# 11_-_CPU_-_POWER.net
KiCad netlist of a schematic drawn in Altium Designer
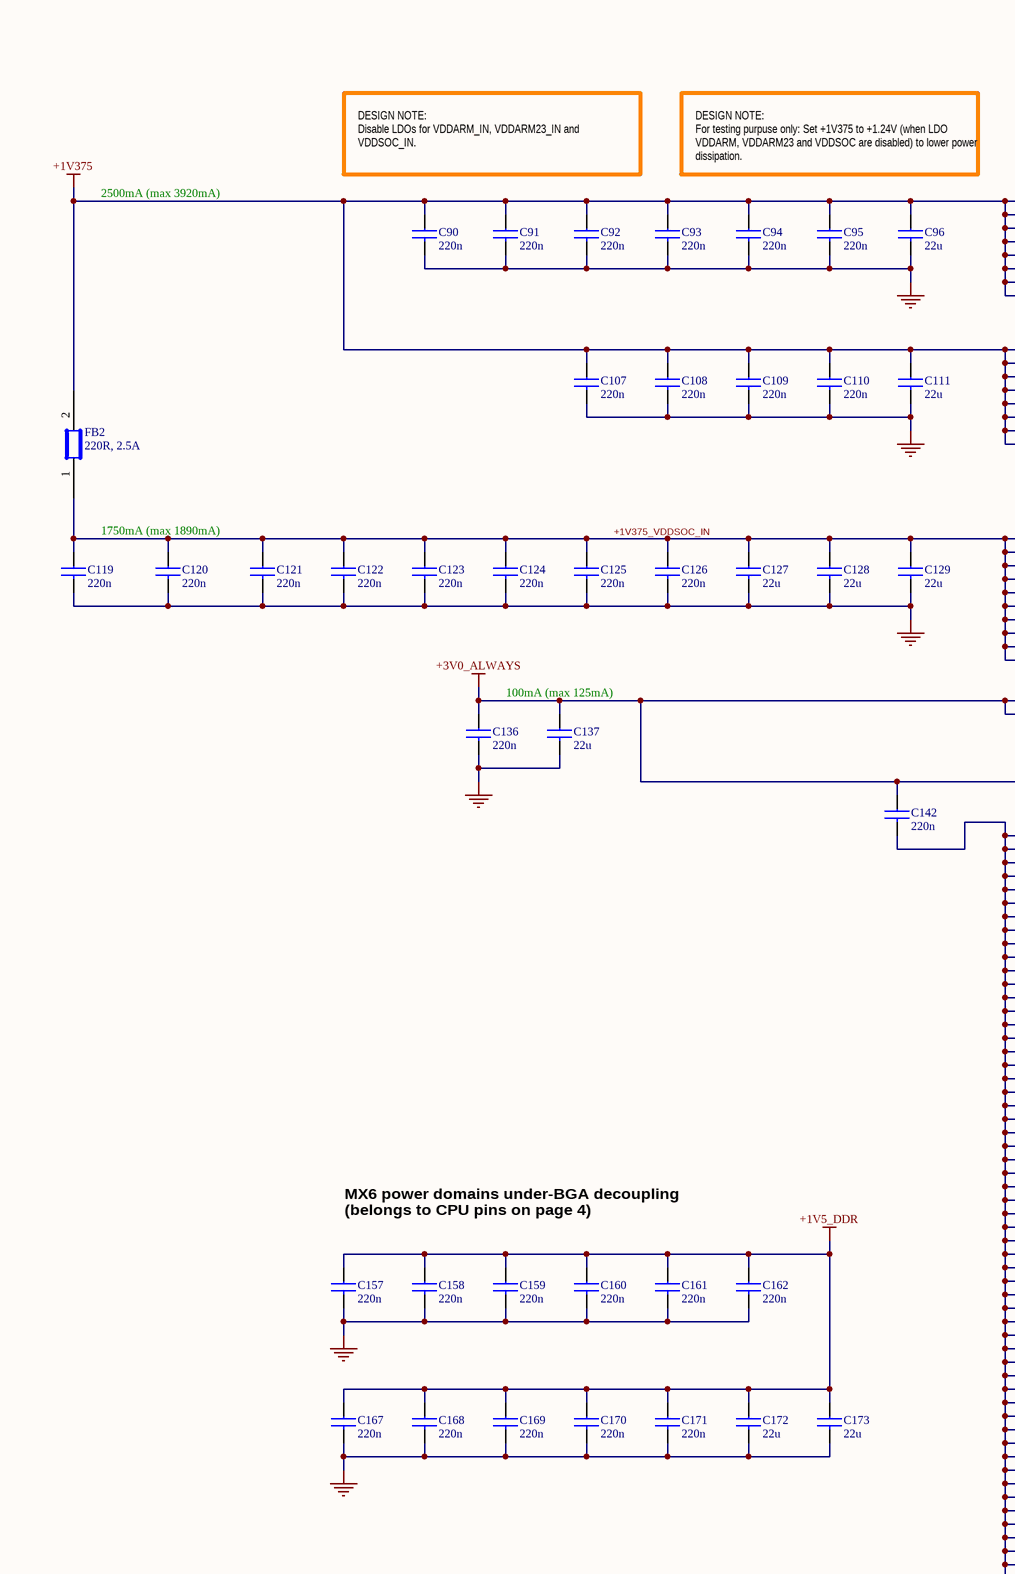
[diagram p0: [11] - CPU - POWER.SchDoc, left]
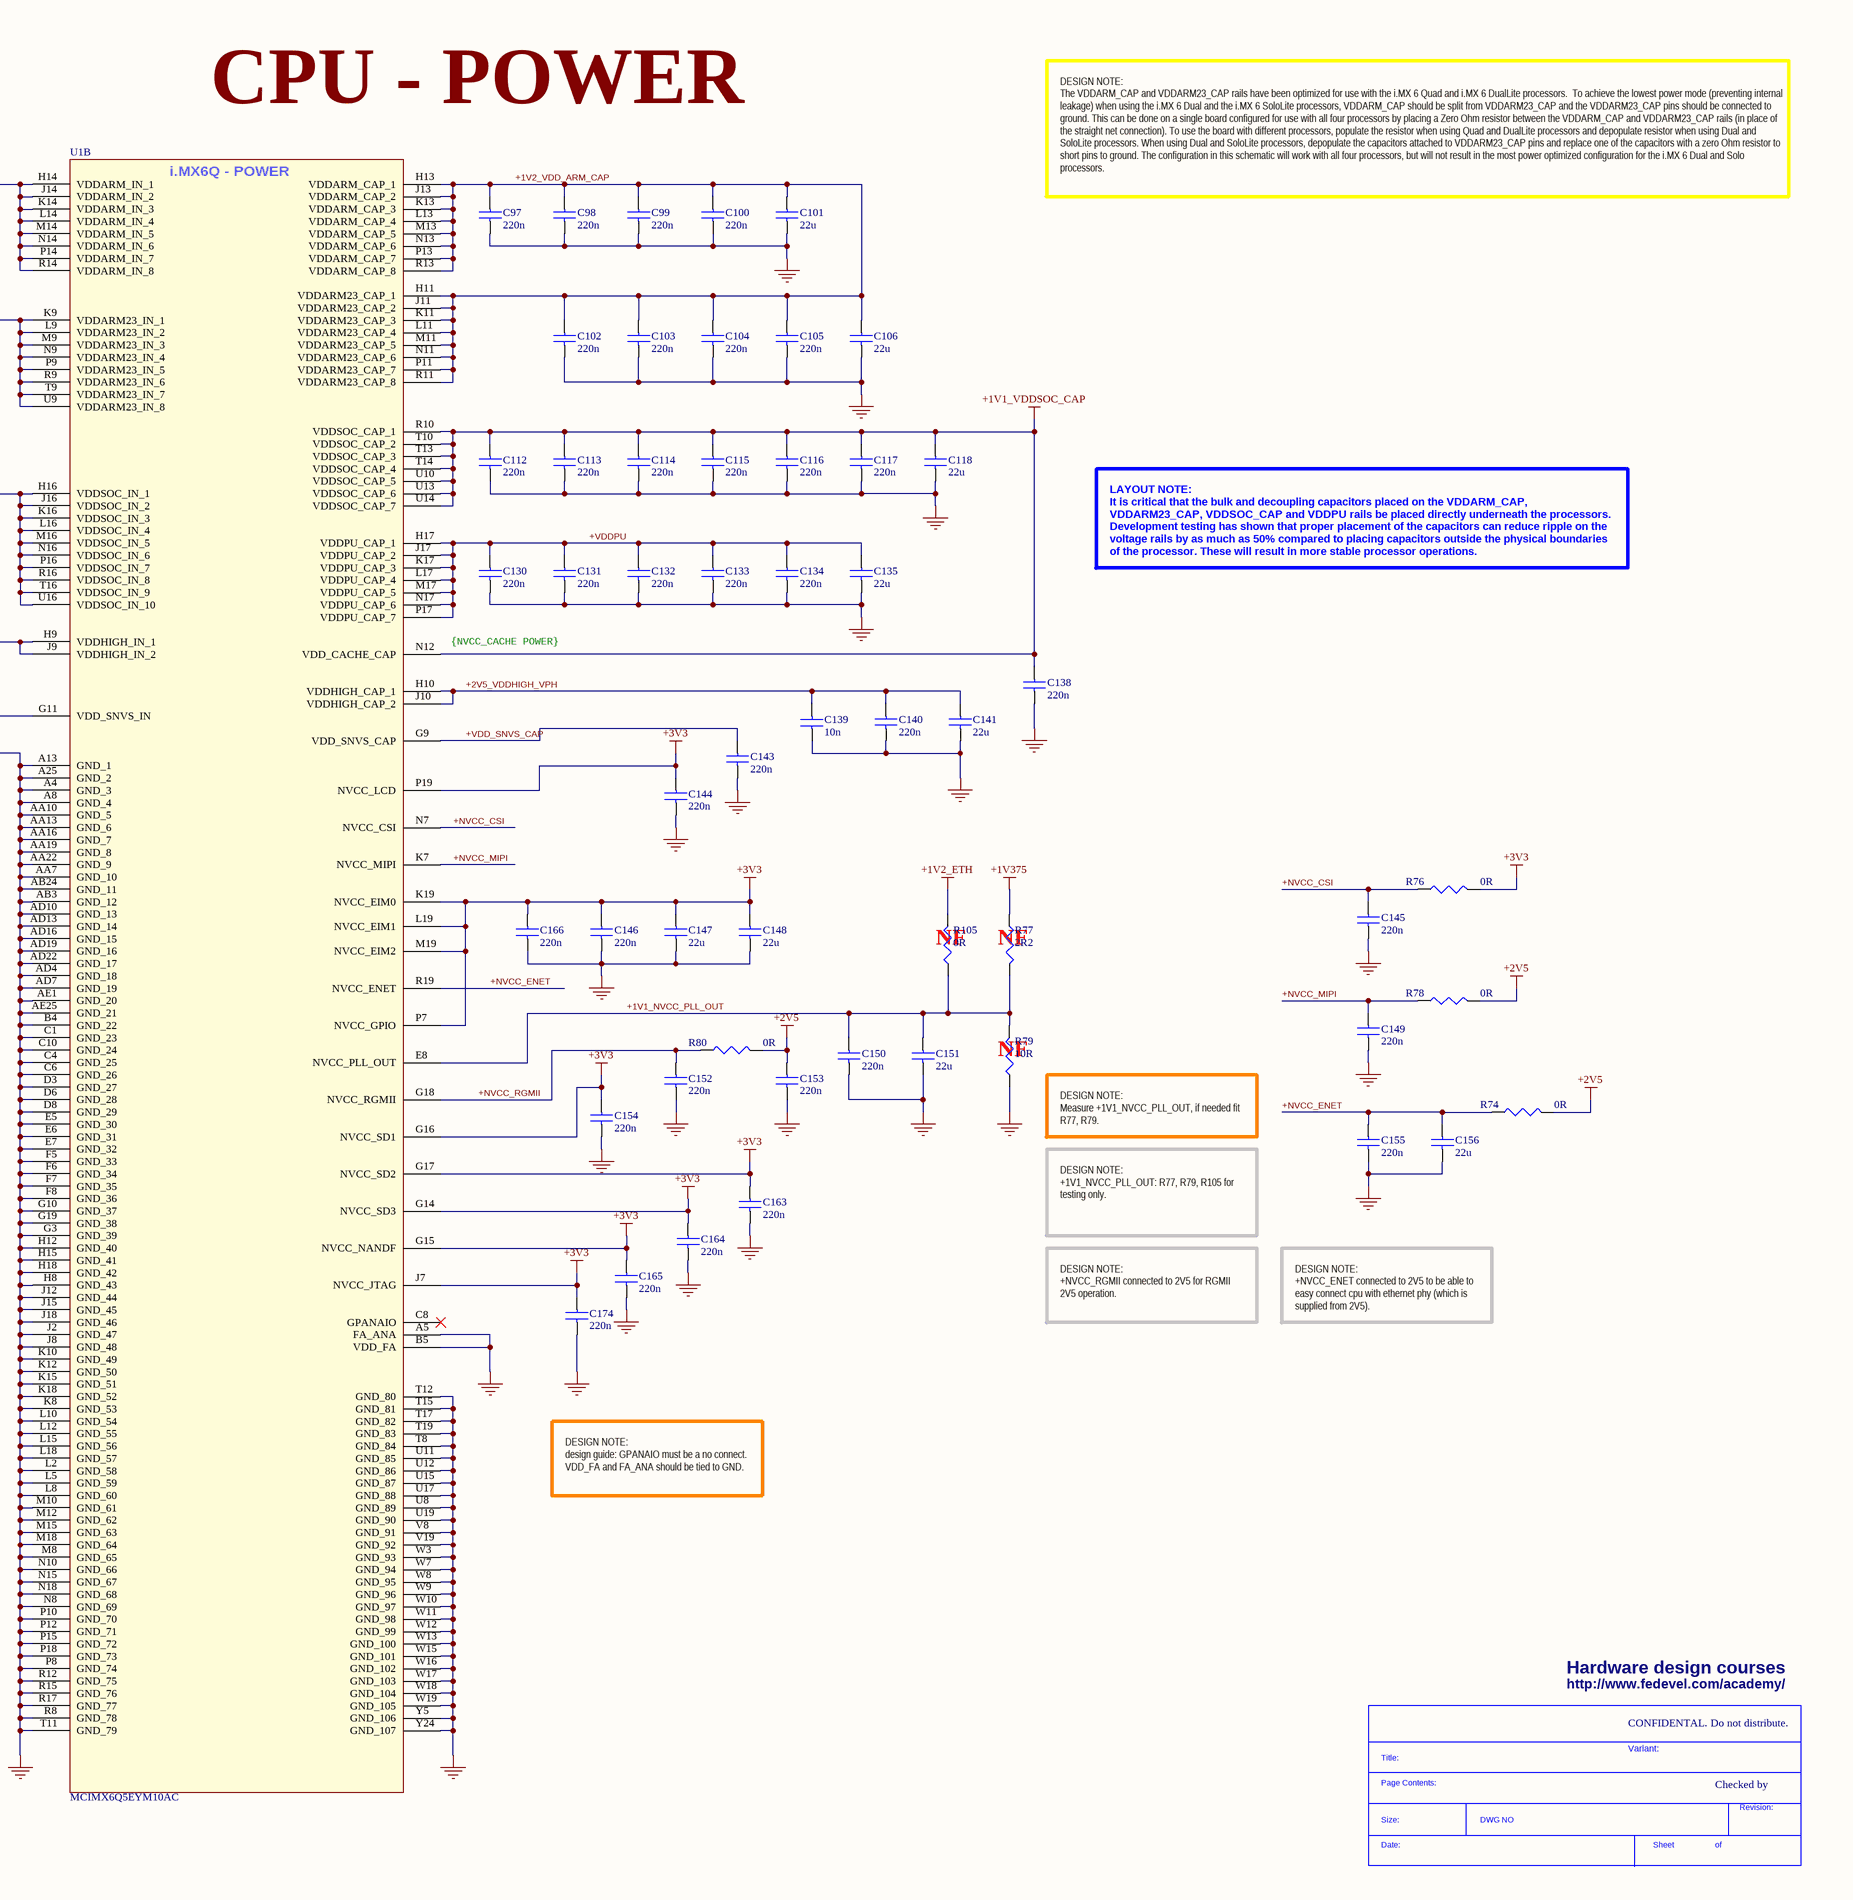
[diagram p1: [11] - CPU - POWER.SchDoc, right]

(export (version "E")
  (design (tool "Eeschema 10.0.6"))
  (components
    (comp (ref "C90")
      (value "220n")
      (footprint "C0402")
      (description "CAP CER .22UF 25V X5R 20% 0402")
      (fields
        (field (name "MANUFACTURER") "TDK Corporation")
        (field (name "MANUFACTURER PART NUMBER") "C1005X5R1E224M")
      )
      (libsource (lib "iMX6 Rex_V1I1") (part "C1005X5R1E224M"))
    )
    (comp (ref "C91")
      (value "220n")
      (footprint "C0402")
      (description "CAP CER .22UF 25V X5R 20% 0402")
      (fields
        (field (name "MANUFACTURER") "TDK Corporation")
        (field (name "MANUFACTURER PART NUMBER") "C1005X5R1E224M")
      )
      (libsource (lib "iMX6 Rex_V1I1") (part "C1005X5R1E224M"))
    )
    (comp (ref "C92")
      (value "220n")
      (footprint "C0402")
      (description "CAP CER .22UF 25V X5R 20% 0402")
      (fields
        (field (name "MANUFACTURER") "TDK Corporation")
        (field (name "MANUFACTURER PART NUMBER") "C1005X5R1E224M")
      )
      (libsource (lib "iMX6 Rex_V1I1") (part "C1005X5R1E224M"))
    )
    (comp (ref "C93")
      (value "220n")
      (footprint "C0402")
      (description "CAP CER .22UF 25V X5R 20% 0402")
      (fields
        (field (name "MANUFACTURER") "TDK Corporation")
        (field (name "MANUFACTURER PART NUMBER") "C1005X5R1E224M")
      )
      (libsource (lib "iMX6 Rex_V1I1") (part "C1005X5R1E224M"))
    )
    (comp (ref "C94")
      (value "220n")
      (footprint "C0402")
      (description "CAP CER .22UF 25V X5R 20% 0402")
      (fields
        (field (name "MANUFACTURER") "TDK Corporation")
        (field (name "MANUFACTURER PART NUMBER") "C1005X5R1E224M")
      )
      (libsource (lib "iMX6 Rex_V1I1") (part "C1005X5R1E224M"))
    )
    (comp (ref "C95")
      (value "220n")
      (footprint "C0402")
      (description "CAP CER .22UF 25V X5R 20% 0402")
      (fields
        (field (name "MANUFACTURER") "TDK Corporation")
        (field (name "MANUFACTURER PART NUMBER") "C1005X5R1E224M")
      )
      (libsource (lib "iMX6 Rex_V1I1") (part "C1005X5R1E224M"))
    )
    (comp (ref "C96")
      (value "22u")
      (footprint "C0603")
      (description "CAP CER 22UF 4V 20% X5R 0603")
      (fields
        (field (name "MANUFACTURER") "Murata Electronics North America")
        (field (name "MANUFACTURER PART NUMBER") "GRM188R60G226MEA0L")
        (field (name ".CHECKED PCB") "RF, used by MM")
        (field (name ".CHECKED SCH") "MM, checked by RF")
        (field (name ".CREATOR") "MM")
      )
      (libsource (lib "iMX6 Rex_V1I1") (part "GRM188R60G226MEA0L"))
    )
    (comp (ref "C97")
      (value "220n")
      (footprint "C0402")
      (description "CAP CER .22UF 25V X5R 20% 0402")
      (fields
        (field (name "MANUFACTURER") "TDK Corporation")
        (field (name "MANUFACTURER PART NUMBER") "C1005X5R1E224M")
      )
      (libsource (lib "iMX6 Rex_V1I1") (part "C1005X5R1E224M"))
    )
    (comp (ref "C98")
      (value "220n")
      (footprint "C0402")
      (description "CAP CER .22UF 25V X5R 20% 0402")
      (fields
        (field (name "MANUFACTURER") "TDK Corporation")
        (field (name "MANUFACTURER PART NUMBER") "C1005X5R1E224M")
      )
      (libsource (lib "iMX6 Rex_V1I1") (part "C1005X5R1E224M"))
    )
    (comp (ref "C99")
      (value "220n")
      (footprint "C0402")
      (description "CAP CER .22UF 25V X5R 20% 0402")
      (fields
        (field (name "MANUFACTURER") "TDK Corporation")
        (field (name "MANUFACTURER PART NUMBER") "C1005X5R1E224M")
      )
      (libsource (lib "iMX6 Rex_V1I1") (part "C1005X5R1E224M"))
    )
    (comp (ref "C100")
      (value "220n")
      (footprint "C0402")
      (description "CAP CER .22UF 25V X5R 20% 0402")
      (fields
        (field (name "MANUFACTURER") "TDK Corporation")
        (field (name "MANUFACTURER PART NUMBER") "C1005X5R1E224M")
      )
      (libsource (lib "iMX6 Rex_V1I1") (part "C1005X5R1E224M"))
    )
    (comp (ref "C101")
      (value "22u")
      (footprint "C0603")
      (description "CAP CER 22UF 4V 20% X5R 0603")
      (fields
        (field (name "MANUFACTURER") "Murata Electronics North America")
        (field (name "MANUFACTURER PART NUMBER") "GRM188R60G226MEA0L")
        (field (name ".CHECKED PCB") "RF, used by MM")
        (field (name ".CHECKED SCH") "MM, checked by RF")
        (field (name ".CREATOR") "MM")
      )
      (libsource (lib "iMX6 Rex_V1I1") (part "GRM188R60G226MEA0L"))
    )
    (comp (ref "C102")
      (value "220n")
      (footprint "C0402")
      (description "CAP CER .22UF 25V X5R 20% 0402")
      (fields
        (field (name "MANUFACTURER") "TDK Corporation")
        (field (name "MANUFACTURER PART NUMBER") "C1005X5R1E224M")
      )
      (libsource (lib "iMX6 Rex_V1I1") (part "C1005X5R1E224M"))
    )
    (comp (ref "C103")
      (value "220n")
      (footprint "C0402")
      (description "CAP CER .22UF 25V X5R 20% 0402")
      (fields
        (field (name "MANUFACTURER") "TDK Corporation")
        (field (name "MANUFACTURER PART NUMBER") "C1005X5R1E224M")
      )
      (libsource (lib "iMX6 Rex_V1I1") (part "C1005X5R1E224M"))
    )
    (comp (ref "C104")
      (value "220n")
      (footprint "C0402")
      (description "CAP CER .22UF 25V X5R 20% 0402")
      (fields
        (field (name "MANUFACTURER") "TDK Corporation")
        (field (name "MANUFACTURER PART NUMBER") "C1005X5R1E224M")
      )
      (libsource (lib "iMX6 Rex_V1I1") (part "C1005X5R1E224M"))
    )
    (comp (ref "C105")
      (value "220n")
      (footprint "C0402")
      (description "CAP CER .22UF 25V X5R 20% 0402")
      (fields
        (field (name "MANUFACTURER") "TDK Corporation")
        (field (name "MANUFACTURER PART NUMBER") "C1005X5R1E224M")
      )
      (libsource (lib "iMX6 Rex_V1I1") (part "C1005X5R1E224M"))
    )
    (comp (ref "C106")
      (value "22u")
      (footprint "C0603")
      (description "CAP CER 22UF 4V 20% X5R 0603")
      (fields
        (field (name "MANUFACTURER") "Murata Electronics North America")
        (field (name "MANUFACTURER PART NUMBER") "GRM188R60G226MEA0L")
        (field (name ".CHECKED PCB") "RF, used by MM")
        (field (name ".CHECKED SCH") "MM, checked by RF")
        (field (name ".CREATOR") "MM")
      )
      (libsource (lib "iMX6 Rex_V1I1") (part "GRM188R60G226MEA0L"))
    )
    (comp (ref "C107")
      (value "220n")
      (footprint "C0402")
      (description "CAP CER .22UF 25V X5R 20% 0402")
      (fields
        (field (name "MANUFACTURER") "TDK Corporation")
        (field (name "MANUFACTURER PART NUMBER") "C1005X5R1E224M")
      )
      (libsource (lib "iMX6 Rex_V1I1") (part "C1005X5R1E224M"))
    )
    (comp (ref "C108")
      (value "220n")
      (footprint "C0402")
      (description "CAP CER .22UF 25V X5R 20% 0402")
      (fields
        (field (name "MANUFACTURER") "TDK Corporation")
        (field (name "MANUFACTURER PART NUMBER") "C1005X5R1E224M")
      )
      (libsource (lib "iMX6 Rex_V1I1") (part "C1005X5R1E224M"))
    )
    (comp (ref "C109")
      (value "220n")
      (footprint "C0402")
      (description "CAP CER .22UF 25V X5R 20% 0402")
      (fields
        (field (name "MANUFACTURER") "TDK Corporation")
        (field (name "MANUFACTURER PART NUMBER") "C1005X5R1E224M")
      )
      (libsource (lib "iMX6 Rex_V1I1") (part "C1005X5R1E224M"))
    )
    (comp (ref "C110")
      (value "220n")
      (footprint "C0402")
      (description "CAP CER .22UF 25V X5R 20% 0402")
      (fields
        (field (name "MANUFACTURER") "TDK Corporation")
        (field (name "MANUFACTURER PART NUMBER") "C1005X5R1E224M")
      )
      (libsource (lib "iMX6 Rex_V1I1") (part "C1005X5R1E224M"))
    )
    (comp (ref "C111")
      (value "22u")
      (footprint "C0603")
      (description "CAP CER 22UF 4V 20% X5R 0603")
      (fields
        (field (name "MANUFACTURER") "Murata Electronics North America")
        (field (name "MANUFACTURER PART NUMBER") "GRM188R60G226MEA0L")
        (field (name ".CHECKED PCB") "RF, used by MM")
        (field (name ".CHECKED SCH") "MM, checked by RF")
        (field (name ".CREATOR") "MM")
      )
      (libsource (lib "iMX6 Rex_V1I1") (part "GRM188R60G226MEA0L"))
    )
    (comp (ref "C112")
      (value "220n")
      (footprint "C0402")
      (description "CAP CER .22UF 25V X5R 20% 0402")
      (fields
        (field (name "MANUFACTURER") "TDK Corporation")
        (field (name "MANUFACTURER PART NUMBER") "C1005X5R1E224M")
      )
      (libsource (lib "iMX6 Rex_V1I1") (part "C1005X5R1E224M"))
    )
    (comp (ref "C113")
      (value "220n")
      (footprint "C0402")
      (description "CAP CER .22UF 25V X5R 20% 0402")
      (fields
        (field (name "MANUFACTURER") "TDK Corporation")
        (field (name "MANUFACTURER PART NUMBER") "C1005X5R1E224M")
      )
      (libsource (lib "iMX6 Rex_V1I1") (part "C1005X5R1E224M"))
    )
    (comp (ref "C114")
      (value "220n")
      (footprint "C0402")
      (description "CAP CER .22UF 25V X5R 20% 0402")
      (fields
        (field (name "MANUFACTURER") "TDK Corporation")
        (field (name "MANUFACTURER PART NUMBER") "C1005X5R1E224M")
      )
      (libsource (lib "iMX6 Rex_V1I1") (part "C1005X5R1E224M"))
    )
    (comp (ref "C115")
      (value "220n")
      (footprint "C0402")
      (description "CAP CER .22UF 25V X5R 20% 0402")
      (fields
        (field (name "MANUFACTURER") "TDK Corporation")
        (field (name "MANUFACTURER PART NUMBER") "C1005X5R1E224M")
      )
      (libsource (lib "iMX6 Rex_V1I1") (part "C1005X5R1E224M"))
    )
    (comp (ref "C116")
      (value "220n")
      (footprint "C0402")
      (description "CAP CER .22UF 25V X5R 20% 0402")
      (fields
        (field (name "MANUFACTURER") "TDK Corporation")
        (field (name "MANUFACTURER PART NUMBER") "C1005X5R1E224M")
      )
      (libsource (lib "iMX6 Rex_V1I1") (part "C1005X5R1E224M"))
    )
    (comp (ref "C117")
      (value "220n")
      (footprint "C0402")
      (description "CAP CER .22UF 25V X5R 20% 0402")
      (fields
        (field (name "MANUFACTURER") "TDK Corporation")
        (field (name "MANUFACTURER PART NUMBER") "C1005X5R1E224M")
      )
      (libsource (lib "iMX6 Rex_V1I1") (part "C1005X5R1E224M"))
    )
    (comp (ref "C118")
      (value "22u")
      (footprint "C0603")
      (description "CAP CER 22UF 4V 20% X5R 0603")
      (fields
        (field (name "MANUFACTURER") "Murata Electronics North America")
        (field (name "MANUFACTURER PART NUMBER") "GRM188R60G226MEA0L")
        (field (name ".CHECKED PCB") "RF, used by MM")
        (field (name ".CHECKED SCH") "MM, checked by RF")
        (field (name ".CREATOR") "MM")
      )
      (libsource (lib "iMX6 Rex_V1I1") (part "GRM188R60G226MEA0L"))
    )
    (comp (ref "C119")
      (value "220n")
      (footprint "C0402")
      (description "CAP CER .22UF 25V X5R 20% 0402")
      (fields
        (field (name "MANUFACTURER") "TDK Corporation")
        (field (name "MANUFACTURER PART NUMBER") "C1005X5R1E224M")
      )
      (libsource (lib "iMX6 Rex_V1I1") (part "C1005X5R1E224M"))
    )
    (comp (ref "C120")
      (value "220n")
      (footprint "C0402")
      (description "CAP CER .22UF 25V X5R 20% 0402")
      (fields
        (field (name "MANUFACTURER") "TDK Corporation")
        (field (name "MANUFACTURER PART NUMBER") "C1005X5R1E224M")
      )
      (libsource (lib "iMX6 Rex_V1I1") (part "C1005X5R1E224M"))
    )
    (comp (ref "C121")
      (value "220n")
      (footprint "C0402")
      (description "CAP CER .22UF 25V X5R 20% 0402")
      (fields
        (field (name "MANUFACTURER") "TDK Corporation")
        (field (name "MANUFACTURER PART NUMBER") "C1005X5R1E224M")
      )
      (libsource (lib "iMX6 Rex_V1I1") (part "C1005X5R1E224M"))
    )
    (comp (ref "C122")
      (value "220n")
      (footprint "C0402")
      (description "CAP CER .22UF 25V X5R 20% 0402")
      (fields
        (field (name "MANUFACTURER") "TDK Corporation")
        (field (name "MANUFACTURER PART NUMBER") "C1005X5R1E224M")
      )
      (libsource (lib "iMX6 Rex_V1I1") (part "C1005X5R1E224M"))
    )
    (comp (ref "C123")
      (value "220n")
      (footprint "C0402")
      (description "CAP CER .22UF 25V X5R 20% 0402")
      (fields
        (field (name "MANUFACTURER") "TDK Corporation")
        (field (name "MANUFACTURER PART NUMBER") "C1005X5R1E224M")
      )
      (libsource (lib "iMX6 Rex_V1I1") (part "C1005X5R1E224M"))
    )
    (comp (ref "C124")
      (value "220n")
      (footprint "C0402")
      (description "CAP CER .22UF 25V X5R 20% 0402")
      (fields
        (field (name "MANUFACTURER") "TDK Corporation")
        (field (name "MANUFACTURER PART NUMBER") "C1005X5R1E224M")
      )
      (libsource (lib "iMX6 Rex_V1I1") (part "C1005X5R1E224M"))
    )
    (comp (ref "C125")
      (value "220n")
      (footprint "C0402")
      (description "CAP CER .22UF 25V X5R 20% 0402")
      (fields
        (field (name "MANUFACTURER") "TDK Corporation")
        (field (name "MANUFACTURER PART NUMBER") "C1005X5R1E224M")
      )
      (libsource (lib "iMX6 Rex_V1I1") (part "C1005X5R1E224M"))
    )
    (comp (ref "C126")
      (value "220n")
      (footprint "C0402")
      (description "CAP CER .22UF 25V X5R 20% 0402")
      (fields
        (field (name "MANUFACTURER") "TDK Corporation")
        (field (name "MANUFACTURER PART NUMBER") "C1005X5R1E224M")
      )
      (libsource (lib "iMX6 Rex_V1I1") (part "C1005X5R1E224M"))
    )
    (comp (ref "C127")
      (value "22u")
      (footprint "C0603")
      (description "CAP CER 22UF 4V 20% X5R 0603")
      (fields
        (field (name "MANUFACTURER") "Murata Electronics North America")
        (field (name "MANUFACTURER PART NUMBER") "GRM188R60G226MEA0L")
        (field (name ".CHECKED PCB") "RF, used by MM")
        (field (name ".CHECKED SCH") "MM, checked by RF")
        (field (name ".CREATOR") "MM")
      )
      (libsource (lib "iMX6 Rex_V1I1") (part "GRM188R60G226MEA0L"))
    )
    (comp (ref "C128")
      (value "22u")
      (footprint "C0603")
      (description "CAP CER 22UF 4V 20% X5R 0603")
      (fields
        (field (name "MANUFACTURER") "Murata Electronics North America")
        (field (name "MANUFACTURER PART NUMBER") "GRM188R60G226MEA0L")
        (field (name ".CHECKED PCB") "RF, used by MM")
        (field (name ".CHECKED SCH") "MM, checked by RF")
        (field (name ".CREATOR") "MM")
      )
      (libsource (lib "iMX6 Rex_V1I1") (part "GRM188R60G226MEA0L"))
    )
    (comp (ref "C129")
      (value "22u")
      (footprint "C0603")
      (description "CAP CER 22UF 4V 20% X5R 0603")
      (fields
        (field (name "MANUFACTURER") "Murata Electronics North America")
        (field (name "MANUFACTURER PART NUMBER") "GRM188R60G226MEA0L")
        (field (name ".CHECKED PCB") "RF, used by MM")
        (field (name ".CHECKED SCH") "MM, checked by RF")
        (field (name ".CREATOR") "MM")
      )
      (libsource (lib "iMX6 Rex_V1I1") (part "GRM188R60G226MEA0L"))
    )
    (comp (ref "C130")
      (value "220n")
      (footprint "C0402")
      (description "CAP CER .22UF 25V X5R 20% 0402")
      (fields
        (field (name "MANUFACTURER") "TDK Corporation")
        (field (name "MANUFACTURER PART NUMBER") "C1005X5R1E224M")
      )
      (libsource (lib "iMX6 Rex_V1I1") (part "C1005X5R1E224M"))
    )
    (comp (ref "C131")
      (value "220n")
      (footprint "C0402")
      (description "CAP CER .22UF 25V X5R 20% 0402")
      (fields
        (field (name "MANUFACTURER") "TDK Corporation")
        (field (name "MANUFACTURER PART NUMBER") "C1005X5R1E224M")
      )
      (libsource (lib "iMX6 Rex_V1I1") (part "C1005X5R1E224M"))
    )
    (comp (ref "C132")
      (value "220n")
      (footprint "C0402")
      (description "CAP CER .22UF 25V X5R 20% 0402")
      (fields
        (field (name "MANUFACTURER") "TDK Corporation")
        (field (name "MANUFACTURER PART NUMBER") "C1005X5R1E224M")
      )
      (libsource (lib "iMX6 Rex_V1I1") (part "C1005X5R1E224M"))
    )
    (comp (ref "C133")
      (value "220n")
      (footprint "C0402")
      (description "CAP CER .22UF 25V X5R 20% 0402")
      (fields
        (field (name "MANUFACTURER") "TDK Corporation")
        (field (name "MANUFACTURER PART NUMBER") "C1005X5R1E224M")
      )
      (libsource (lib "iMX6 Rex_V1I1") (part "C1005X5R1E224M"))
    )
    (comp (ref "C134")
      (value "220n")
      (footprint "C0402")
      (description "CAP CER .22UF 25V X5R 20% 0402")
      (fields
        (field (name "MANUFACTURER") "TDK Corporation")
        (field (name "MANUFACTURER PART NUMBER") "C1005X5R1E224M")
      )
      (libsource (lib "iMX6 Rex_V1I1") (part "C1005X5R1E224M"))
    )
    (comp (ref "C135")
      (value "22u")
      (footprint "C0603")
      (description "CAP CER 22UF 4V 20% X5R 0603")
      (fields
        (field (name "MANUFACTURER") "Murata Electronics North America")
        (field (name "MANUFACTURER PART NUMBER") "GRM188R60G226MEA0L")
        (field (name ".CHECKED PCB") "RF, used by MM")
        (field (name ".CHECKED SCH") "MM, checked by RF")
        (field (name ".CREATOR") "MM")
      )
      (libsource (lib "iMX6 Rex_V1I1") (part "GRM188R60G226MEA0L"))
    )
    (comp (ref "C136")
      (value "220n")
      (footprint "C0402")
      (description "CAP CER .22UF 25V X5R 20% 0402")
      (fields
        (field (name "MANUFACTURER") "TDK Corporation")
        (field (name "MANUFACTURER PART NUMBER") "C1005X5R1E224M")
      )
      (libsource (lib "iMX6 Rex_V1I1") (part "C1005X5R1E224M"))
    )
    (comp (ref "C137")
      (value "22u")
      (footprint "C0805")
      (description "CAP CER 22UF 16V 10% X5R 0805")
      (fields
        (field (name "MANUFACTURER") "TDK Corporation")
        (field (name "MANUFACTURER PART NUMBER") "C2012X5R1C226K")
        (field (name ".CHECKED PCB") "RF")
        (field (name ".CHECKED SCH") "RF")
      )
      (libsource (lib "iMX6 Rex_V1I1") (part "C2012X5R1C226K"))
    )
    (comp (ref "C138")
      (value "220n")
      (footprint "C0402")
      (description "CAP CER .22UF 25V X5R 20% 0402")
      (fields
        (field (name "MANUFACTURER") "TDK Corporation")
        (field (name "MANUFACTURER PART NUMBER") "C1005X5R1E224M")
      )
      (libsource (lib "iMX6 Rex_V1I1") (part "C1005X5R1E224M"))
    )
    (comp (ref "C139")
      (value "10n")
      (footprint "C0402")
      (description "CAP CER 10000PF 16V X7R 10% 0402")
      (fields
        (field (name "MANUFACTURER") "TDK Corporation")
        (field (name "MANUFACTURER PART NUMBER") "C1005X7R1C103K")
      )
      (libsource (lib "iMX6 Rex_V1I1") (part "C1005X7R1C103K"))
    )
    (comp (ref "C140")
      (value "220n")
      (footprint "C0402")
      (description "CAP CER .22UF 25V X5R 20% 0402")
      (fields
        (field (name "MANUFACTURER") "TDK Corporation")
        (field (name "MANUFACTURER PART NUMBER") "C1005X5R1E224M")
      )
      (libsource (lib "iMX6 Rex_V1I1") (part "C1005X5R1E224M"))
    )
    (comp (ref "C141")
      (value "22u")
      (footprint "C0805")
      (description "CAP CER 22UF 16V 10% X5R 0805")
      (fields
        (field (name "MANUFACTURER") "TDK Corporation")
        (field (name "MANUFACTURER PART NUMBER") "C2012X5R1C226K")
        (field (name ".CHECKED PCB") "RF")
        (field (name ".CHECKED SCH") "RF")
      )
      (libsource (lib "iMX6 Rex_V1I1") (part "C2012X5R1C226K"))
    )
    (comp (ref "C142")
      (value "220n")
      (footprint "C0402")
      (description "CAP CER .22UF 25V X5R 20% 0402")
      (fields
        (field (name "MANUFACTURER") "TDK Corporation")
        (field (name "MANUFACTURER PART NUMBER") "C1005X5R1E224M")
      )
      (libsource (lib "iMX6 Rex_V1I1") (part "C1005X5R1E224M"))
    )
    (comp (ref "C143")
      (value "220n")
      (footprint "C0402")
      (description "CAP CER .22UF 25V X5R 20% 0402")
      (fields
        (field (name "MANUFACTURER") "TDK Corporation")
        (field (name "MANUFACTURER PART NUMBER") "C1005X5R1E224M")
      )
      (libsource (lib "iMX6 Rex_V1I1") (part "C1005X5R1E224M"))
    )
    (comp (ref "C144")
      (value "220n")
      (footprint "C0402")
      (description "CAP CER .22UF 25V X5R 20% 0402")
      (fields
        (field (name "MANUFACTURER") "TDK Corporation")
        (field (name "MANUFACTURER PART NUMBER") "C1005X5R1E224M")
      )
      (libsource (lib "iMX6 Rex_V1I1") (part "C1005X5R1E224M"))
    )
    (comp (ref "C145")
      (value "220n")
      (footprint "C0402")
      (description "CAP CER .22UF 25V X5R 20% 0402")
      (fields
        (field (name "MANUFACTURER") "TDK Corporation")
        (field (name "MANUFACTURER PART NUMBER") "C1005X5R1E224M")
      )
      (libsource (lib "iMX6 Rex_V1I1") (part "C1005X5R1E224M"))
    )
    (comp (ref "C146")
      (value "220n")
      (footprint "C0402")
      (description "CAP CER .22UF 25V X5R 20% 0402")
      (fields
        (field (name "MANUFACTURER") "TDK Corporation")
        (field (name "MANUFACTURER PART NUMBER") "C1005X5R1E224M")
      )
      (libsource (lib "iMX6 Rex_V1I1") (part "C1005X5R1E224M"))
    )
    (comp (ref "C147")
      (value "22u")
      (footprint "C0805")
      (description "CAP CER 22UF 16V 10% X5R 0805")
      (fields
        (field (name "MANUFACTURER") "TDK Corporation")
        (field (name "MANUFACTURER PART NUMBER") "C2012X5R1C226K")
        (field (name ".CHECKED PCB") "RF")
        (field (name ".CHECKED SCH") "RF")
      )
      (libsource (lib "iMX6 Rex_V1I1") (part "C2012X5R1C226K"))
    )
    (comp (ref "C148")
      (value "22u")
      (footprint "C0805")
      (description "CAP CER 22UF 16V 10% X5R 0805")
      (fields
        (field (name "MANUFACTURER") "TDK Corporation")
        (field (name "MANUFACTURER PART NUMBER") "C2012X5R1C226K")
        (field (name ".CHECKED PCB") "RF")
        (field (name ".CHECKED SCH") "RF")
      )
      (libsource (lib "iMX6 Rex_V1I1") (part "C2012X5R1C226K"))
    )
    (comp (ref "C149")
      (value "220n")
      (footprint "C0402")
      (description "CAP CER .22UF 25V X5R 20% 0402")
      (fields
        (field (name "MANUFACTURER") "TDK Corporation")
        (field (name "MANUFACTURER PART NUMBER") "C1005X5R1E224M")
      )
      (libsource (lib "iMX6 Rex_V1I1") (part "C1005X5R1E224M"))
    )
    (comp (ref "C150")
      (value "220n")
      (footprint "C0402")
      (description "CAP CER .22UF 25V X5R 20% 0402")
      (fields
        (field (name "MANUFACTURER") "TDK Corporation")
        (field (name "MANUFACTURER PART NUMBER") "C1005X5R1E224M")
      )
      (libsource (lib "iMX6 Rex_V1I1") (part "C1005X5R1E224M"))
    )
    (comp (ref "C151")
      (value "22u")
      (footprint "C0603")
      (description "CAP CER 22UF 4V 20% X5R 0603")
      (fields
        (field (name "MANUFACTURER") "Murata Electronics North America")
        (field (name "MANUFACTURER PART NUMBER") "GRM188R60G226MEA0L")
        (field (name ".CHECKED PCB") "RF, used by MM")
        (field (name ".CHECKED SCH") "MM, checked by RF")
        (field (name ".CREATOR") "MM")
      )
      (libsource (lib "iMX6 Rex_V1I1") (part "GRM188R60G226MEA0L"))
    )
    (comp (ref "C152")
      (value "220n")
      (footprint "C0402")
      (description "CAP CER .22UF 25V X5R 20% 0402")
      (fields
        (field (name "MANUFACTURER") "TDK Corporation")
        (field (name "MANUFACTURER PART NUMBER") "C1005X5R1E224M")
      )
      (libsource (lib "iMX6 Rex_V1I1") (part "C1005X5R1E224M"))
    )
    (comp (ref "C153")
      (value "220n")
      (footprint "C0402")
      (description "CAP CER .22UF 25V X5R 20% 0402")
      (fields
        (field (name "MANUFACTURER") "TDK Corporation")
        (field (name "MANUFACTURER PART NUMBER") "C1005X5R1E224M")
      )
      (libsource (lib "iMX6 Rex_V1I1") (part "C1005X5R1E224M"))
    )
    (comp (ref "C154")
      (value "220n")
      (footprint "C0402")
      (description "CAP CER .22UF 25V X5R 20% 0402")
      (fields
        (field (name "MANUFACTURER") "TDK Corporation")
        (field (name "MANUFACTURER PART NUMBER") "C1005X5R1E224M")
      )
      (libsource (lib "iMX6 Rex_V1I1") (part "C1005X5R1E224M"))
    )
    (comp (ref "C155")
      (value "220n")
      (footprint "C0402")
      (description "CAP CER .22UF 25V X5R 20% 0402")
      (fields
        (field (name "MANUFACTURER") "TDK Corporation")
        (field (name "MANUFACTURER PART NUMBER") "C1005X5R1E224M")
      )
      (libsource (lib "iMX6 Rex_V1I1") (part "C1005X5R1E224M"))
    )
    (comp (ref "C156")
      (value "22u")
      (footprint "C0805")
      (description "CAP CER 22UF 16V 10% X5R 0805")
      (fields
        (field (name "MANUFACTURER") "TDK Corporation")
        (field (name "MANUFACTURER PART NUMBER") "C2012X5R1C226K")
        (field (name ".CHECKED PCB") "RF")
        (field (name ".CHECKED SCH") "RF")
      )
      (libsource (lib "iMX6 Rex_V1I1") (part "C2012X5R1C226K"))
    )
    (comp (ref "C157")
      (value "220n")
      (footprint "C0402")
      (description "CAP CER .22UF 25V X5R 20% 0402")
      (fields
        (field (name "MANUFACTURER") "TDK Corporation")
        (field (name "MANUFACTURER PART NUMBER") "C1005X5R1E224M")
      )
      (libsource (lib "iMX6 Rex_V1I1") (part "C1005X5R1E224M"))
    )
    (comp (ref "C158")
      (value "220n")
      (footprint "C0402")
      (description "CAP CER .22UF 25V X5R 20% 0402")
      (fields
        (field (name "MANUFACTURER") "TDK Corporation")
        (field (name "MANUFACTURER PART NUMBER") "C1005X5R1E224M")
      )
      (libsource (lib "iMX6 Rex_V1I1") (part "C1005X5R1E224M"))
    )
    (comp (ref "C159")
      (value "220n")
      (footprint "C0402")
      (description "CAP CER .22UF 25V X5R 20% 0402")
      (fields
        (field (name "MANUFACTURER") "TDK Corporation")
        (field (name "MANUFACTURER PART NUMBER") "C1005X5R1E224M")
      )
      (libsource (lib "iMX6 Rex_V1I1") (part "C1005X5R1E224M"))
    )
    (comp (ref "C160")
      (value "220n")
      (footprint "C0402")
      (description "CAP CER .22UF 25V X5R 20% 0402")
      (fields
        (field (name "MANUFACTURER") "TDK Corporation")
        (field (name "MANUFACTURER PART NUMBER") "C1005X5R1E224M")
      )
      (libsource (lib "iMX6 Rex_V1I1") (part "C1005X5R1E224M"))
    )
    (comp (ref "C161")
      (value "220n")
      (footprint "C0402")
      (description "CAP CER .22UF 25V X5R 20% 0402")
      (fields
        (field (name "MANUFACTURER") "TDK Corporation")
        (field (name "MANUFACTURER PART NUMBER") "C1005X5R1E224M")
      )
      (libsource (lib "iMX6 Rex_V1I1") (part "C1005X5R1E224M"))
    )
    (comp (ref "C162")
      (value "220n")
      (footprint "C0402")
      (description "CAP CER .22UF 25V X5R 20% 0402")
      (fields
        (field (name "MANUFACTURER") "TDK Corporation")
        (field (name "MANUFACTURER PART NUMBER") "C1005X5R1E224M")
      )
      (libsource (lib "iMX6 Rex_V1I1") (part "C1005X5R1E224M"))
    )
    (comp (ref "C163")
      (value "220n")
      (footprint "C0402")
      (description "CAP CER .22UF 25V X5R 20% 0402")
      (fields
        (field (name "MANUFACTURER") "TDK Corporation")
        (field (name "MANUFACTURER PART NUMBER") "C1005X5R1E224M")
      )
      (libsource (lib "iMX6 Rex_V1I1") (part "C1005X5R1E224M"))
    )
    (comp (ref "C164")
      (value "220n")
      (footprint "C0402")
      (description "CAP CER .22UF 25V X5R 20% 0402")
      (fields
        (field (name "MANUFACTURER") "TDK Corporation")
        (field (name "MANUFACTURER PART NUMBER") "C1005X5R1E224M")
      )
      (libsource (lib "iMX6 Rex_V1I1") (part "C1005X5R1E224M"))
    )
    (comp (ref "C165")
      (value "220n")
      (footprint "C0402")
      (description "CAP CER .22UF 25V X5R 20% 0402")
      (fields
        (field (name "MANUFACTURER") "TDK Corporation")
        (field (name "MANUFACTURER PART NUMBER") "C1005X5R1E224M")
      )
      (libsource (lib "iMX6 Rex_V1I1") (part "C1005X5R1E224M"))
    )
    (comp (ref "C166")
      (value "220n")
      (footprint "C0402")
      (description "CAP CER .22UF 25V X5R 20% 0402")
      (fields
        (field (name "MANUFACTURER") "TDK Corporation")
        (field (name "MANUFACTURER PART NUMBER") "C1005X5R1E224M")
      )
      (libsource (lib "iMX6 Rex_V1I1") (part "C1005X5R1E224M"))
    )
    (comp (ref "C167")
      (value "220n")
      (footprint "C0402")
      (description "CAP CER .22UF 25V X5R 20% 0402")
      (fields
        (field (name "MANUFACTURER") "TDK Corporation")
        (field (name "MANUFACTURER PART NUMBER") "C1005X5R1E224M")
      )
      (libsource (lib "iMX6 Rex_V1I1") (part "C1005X5R1E224M"))
    )
    (comp (ref "C168")
      (value "220n")
      (footprint "C0402")
      (description "CAP CER .22UF 25V X5R 20% 0402")
      (fields
        (field (name "MANUFACTURER") "TDK Corporation")
        (field (name "MANUFACTURER PART NUMBER") "C1005X5R1E224M")
      )
      (libsource (lib "iMX6 Rex_V1I1") (part "C1005X5R1E224M"))
    )
    (comp (ref "C169")
      (value "220n")
      (footprint "C0402")
      (description "CAP CER .22UF 25V X5R 20% 0402")
      (fields
        (field (name "MANUFACTURER") "TDK Corporation")
        (field (name "MANUFACTURER PART NUMBER") "C1005X5R1E224M")
      )
      (libsource (lib "iMX6 Rex_V1I1") (part "C1005X5R1E224M"))
    )
    (comp (ref "C170")
      (value "220n")
      (footprint "C0402")
      (description "CAP CER .22UF 25V X5R 20% 0402")
      (fields
        (field (name "MANUFACTURER") "TDK Corporation")
        (field (name "MANUFACTURER PART NUMBER") "C1005X5R1E224M")
      )
      (libsource (lib "iMX6 Rex_V1I1") (part "C1005X5R1E224M"))
    )
    (comp (ref "C171")
      (value "220n")
      (footprint "C0402")
      (description "CAP CER .22UF 25V X5R 20% 0402")
      (fields
        (field (name "MANUFACTURER") "TDK Corporation")
        (field (name "MANUFACTURER PART NUMBER") "C1005X5R1E224M")
      )
      (libsource (lib "iMX6 Rex_V1I1") (part "C1005X5R1E224M"))
    )
    (comp (ref "C172")
      (value "22u")
      (footprint "C0603")
      (description "CAP CER 22UF 4V 20% X5R 0603")
      (fields
        (field (name "MANUFACTURER") "Murata Electronics North America")
        (field (name "MANUFACTURER PART NUMBER") "GRM188R60G226MEA0L")
        (field (name ".CHECKED PCB") "RF, used by MM")
        (field (name ".CHECKED SCH") "MM, checked by RF")
        (field (name ".CREATOR") "MM")
      )
      (libsource (lib "iMX6 Rex_V1I1") (part "GRM188R60G226MEA0L"))
    )
    (comp (ref "C173")
      (value "22u")
      (footprint "C0603")
      (description "CAP CER 22UF 4V 20% X5R 0603")
      (fields
        (field (name "MANUFACTURER") "Murata Electronics North America")
        (field (name "MANUFACTURER PART NUMBER") "GRM188R60G226MEA0L")
        (field (name ".CHECKED PCB") "RF, used by MM")
        (field (name ".CHECKED SCH") "MM, checked by RF")
        (field (name ".CREATOR") "MM")
      )
      (libsource (lib "iMX6 Rex_V1I1") (part "GRM188R60G226MEA0L"))
    )
    (comp (ref "C174")
      (value "220n")
      (footprint "C0402")
      (description "CAP CER .22UF 25V X5R 20% 0402")
      (fields
        (field (name "MANUFACTURER") "TDK Corporation")
        (field (name "MANUFACTURER PART NUMBER") "C1005X5R1E224M")
      )
      (libsource (lib "iMX6 Rex_V1I1") (part "C1005X5R1E224M"))
    )
    (comp (ref "FB2")
      (value "220R, 2.5A")
      (footprint "C0603")
      (description "FERRITE CHIP 220 OHM 2500MA 0603")
      (fields
        (field (name "MANUFACTURER") "Murata Electronics North America")
        (field (name "MANUFACTURER PART NUMBER") "BLM18SG221TN1D")
        (field (name ".CHECKED PCB") "RF")
        (field (name ".CHECKED SCH") "RF")
      )
      (libsource (lib "iMX6 Rex_V1I1") (part "BLM18SG221TN1D"))
    )
    (comp (ref "R74")
      (value "0R")
      (footprint "R0402")
      (description "RES 0.0 OHM 1/16W 0402 SMD")
      (fields
        (field (name "MANUFACTURER") "Yageo")
        (field (name "MANUFACTURER PART NUMBER") "RC0402JR-070RL")
      )
      (libsource (lib "iMX6 Rex_V1I1") (part "RC0402JR-070RL"))
    )
    (comp (ref "R76")
      (value "0R")
      (footprint "R0402")
      (description "RES 0.0 OHM 1/16W 0402 SMD")
      (fields
        (field (name "MANUFACTURER") "Yageo")
        (field (name "MANUFACTURER PART NUMBER") "RC0402JR-070RL")
      )
      (libsource (lib "iMX6 Rex_V1I1") (part "RC0402JR-070RL"))
    )
    (comp (ref "R77")
      (value "2R2")
      (footprint "R0402")
      (description "RES 2.20 OHM 1/16W 1% 0402 SMD")
      (fields
        (field (name "MANUFACTURER") "Vishay Dale")
        (field (name "MANUFACTURER PART NUMBER") "CRCW04022R20FKED")
        (field (name ".CHECKED PCB") "RF")
        (field (name ".CHECKED SCH") "RF")
      )
      (libsource (lib "iMX6 Rex_V1I1") (part "CRCW04022R20FKED"))
    )
    (comp (ref "R78")
      (value "0R")
      (footprint "R0402")
      (description "RES 0.0 OHM 1/16W 0402 SMD")
      (fields
        (field (name "MANUFACTURER") "Yageo")
        (field (name "MANUFACTURER PART NUMBER") "RC0402JR-070RL")
      )
      (libsource (lib "iMX6 Rex_V1I1") (part "RC0402JR-070RL"))
    )
    (comp (ref "R79")
      (value "10R")
      (footprint "R0402")
      (description "RES 10.0 OHM 1/16W 1% 0402 SMD")
      (fields
        (field (name "MANUFACTURER") "Yageo")
        (field (name "MANUFACTURER PART NUMBER") "RC0402FR-0710RL")
      )
      (libsource (lib "iMX6 Rex_V1I1") (part "RC0402FR-0710RL"))
    )
    (comp (ref "R80")
      (value "0R")
      (footprint "R0402")
      (description "RES 0.0 OHM 1/16W 0402 SMD")
      (fields
        (field (name "MANUFACTURER") "Yageo")
        (field (name "MANUFACTURER PART NUMBER") "RC0402JR-070RL")
      )
      (libsource (lib "iMX6 Rex_V1I1") (part "RC0402JR-070RL"))
    )
    (comp (ref "R105")
      (value "0R")
      (footprint "R0402")
      (description "RES 0.0 OHM 1/16W 0402 SMD")
      (fields
        (field (name "MANUFACTURER") "Yageo")
        (field (name "MANUFACTURER PART NUMBER") "RC0402JR-070RL")
      )
      (libsource (lib "iMX6 Rex_V1I1") (part "RC0402JR-070RL"))
    )
    (comp (ref "U1")
      (value "MCIMX6Q5EYM10AC")
      (footprint "PBGA624")
      (description "IC MCU 32BIT ARM QUAD 624FCBGA")
      (fields
        (field (name "MANUFACTURER") "Freescale Semiconductor")
        (field (name ".CREATOR") "MM")
        (field (name ".CHECKED PCB") "MM, checked by RF")
        (field (name ".CHECKED SCH") "MM")
      )
      (libsource (lib "iMX6 Rex_V1I1") (part "MCIMX6Q5EYM10AC"))
    )
  )
  (nets
    (net (code "1") (name "+1V1_VDDSOC_CAP") (class "Default")
      (node (ref "C112") (pin "1") (pinfunction "1_1") (pintype "passive"))
      (node (ref "C113") (pin "1") (pinfunction "1_1") (pintype "passive"))
      (node (ref "C114") (pin "1") (pinfunction "1_1") (pintype "passive"))
      (node (ref "C115") (pin "1") (pinfunction "1_1") (pintype "passive"))
      (node (ref "C116") (pin "1") (pinfunction "1_1") (pintype "passive"))
      (node (ref "C117") (pin "1") (pinfunction "1_1") (pintype "passive"))
      (node (ref "C118") (pin "1") (pinfunction "1_1") (pintype "passive"))
      (node (ref "C138") (pin "1") (pinfunction "1_1") (pintype "passive"))
      (node (ref "U1") (pin "N12") (pinfunction "VDD_CACHE_CAP_N12") (pintype "power_in"))
      (node (ref "U1") (pin "R10") (pinfunction "VDDSOC_CAP_1_R10") (pintype "power_in"))
      (node (ref "U1") (pin "T10") (pinfunction "VDDSOC_CAP_2_T10") (pintype "power_in"))
      (node (ref "U1") (pin "T13") (pinfunction "VDDSOC_CAP_3_T13") (pintype "power_in"))
      (node (ref "U1") (pin "T14") (pinfunction "VDDSOC_CAP_4_T14") (pintype "power_in"))
      (node (ref "U1") (pin "U10") (pinfunction "VDDSOC_CAP_5_U10") (pintype "power_in"))
      (node (ref "U1") (pin "U13") (pinfunction "VDDSOC_CAP_6_U13") (pintype "power_in"))
      (node (ref "U1") (pin "U14") (pinfunction "VDDSOC_CAP_7_U14") (pintype "power_in"))
    )
    (net (code "2") (name "+1V2_ETH") (class "Default")
      (node (ref "R105") (pin "2") (pinfunction "2_2") (pintype "passive"))
    )
    (net (code "3") (name "+1V5_DDR") (class "Default")
      (node (ref "C157") (pin "1") (pinfunction "1_1") (pintype "passive"))
      (node (ref "C158") (pin "1") (pinfunction "1_1") (pintype "passive"))
      (node (ref "C159") (pin "1") (pinfunction "1_1") (pintype "passive"))
      (node (ref "C160") (pin "1") (pinfunction "1_1") (pintype "passive"))
      (node (ref "C161") (pin "1") (pinfunction "1_1") (pintype "passive"))
      (node (ref "C162") (pin "1") (pinfunction "1_1") (pintype "passive"))
      (node (ref "C167") (pin "1") (pinfunction "1_1") (pintype "passive"))
      (node (ref "C168") (pin "1") (pinfunction "1_1") (pintype "passive"))
      (node (ref "C169") (pin "1") (pinfunction "1_1") (pintype "passive"))
      (node (ref "C170") (pin "1") (pinfunction "1_1") (pintype "passive"))
      (node (ref "C171") (pin "1") (pinfunction "1_1") (pintype "passive"))
      (node (ref "C172") (pin "1") (pinfunction "1_1") (pintype "passive"))
      (node (ref "C173") (pin "1") (pinfunction "1_1") (pintype "passive"))
    )
    (net (code "4") (name "+1V375") (class "Default")
      (node (ref "C107") (pin "1") (pinfunction "1_1") (pintype "passive"))
      (node (ref "C108") (pin "1") (pinfunction "1_1") (pintype "passive"))
      (node (ref "C109") (pin "1") (pinfunction "1_1") (pintype "passive"))
      (node (ref "C110") (pin "1") (pinfunction "1_1") (pintype "passive"))
      (node (ref "C111") (pin "1") (pinfunction "1_1") (pintype "passive"))
      (node (ref "C90") (pin "1") (pinfunction "1_1") (pintype "passive"))
      (node (ref "C91") (pin "1") (pinfunction "1_1") (pintype "passive"))
      (node (ref "C92") (pin "1") (pinfunction "1_1") (pintype "passive"))
      (node (ref "C93") (pin "1") (pinfunction "1_1") (pintype "passive"))
      (node (ref "C94") (pin "1") (pinfunction "1_1") (pintype "passive"))
      (node (ref "C95") (pin "1") (pinfunction "1_1") (pintype "passive"))
      (node (ref "C96") (pin "1") (pinfunction "1_1") (pintype "passive"))
      (node (ref "FB2") (pin "2") (pinfunction "2_2") (pintype "passive"))
      (node (ref "R77") (pin "1") (pinfunction "1_1") (pintype "passive"))
      (node (ref "U1") (pin "H14") (pinfunction "VDDARM_IN_1_H14") (pintype "power_in"))
      (node (ref "U1") (pin "J14") (pinfunction "VDDARM_IN_2_J14") (pintype "power_in"))
      (node (ref "U1") (pin "K14") (pinfunction "VDDARM_IN_3_K14") (pintype "power_in"))
      (node (ref "U1") (pin "K9") (pinfunction "VDDARM23_IN_1_K9") (pintype "power_in"))
      (node (ref "U1") (pin "L14") (pinfunction "VDDARM_IN_4_L14") (pintype "power_in"))
      (node (ref "U1") (pin "L9") (pinfunction "VDDARM23_IN_2_L9") (pintype "power_in"))
      (node (ref "U1") (pin "M14") (pinfunction "VDDARM_IN_5_M14") (pintype "power_in"))
      (node (ref "U1") (pin "M9") (pinfunction "VDDARM23_IN_3_M9") (pintype "power_in"))
      (node (ref "U1") (pin "N14") (pinfunction "VDDARM_IN_6_N14") (pintype "power_in"))
      (node (ref "U1") (pin "N9") (pinfunction "VDDARM23_IN_4_N9") (pintype "power_in"))
      (node (ref "U1") (pin "P14") (pinfunction "VDDARM_IN_7_P14") (pintype "power_in"))
      (node (ref "U1") (pin "P9") (pinfunction "VDDARM23_IN_5_P9") (pintype "power_in"))
      (node (ref "U1") (pin "R14") (pinfunction "VDDARM_IN_8_R14") (pintype "power_in"))
      (node (ref "U1") (pin "R9") (pinfunction "VDDARM23_IN_6_R9") (pintype "power_in"))
      (node (ref "U1") (pin "T9") (pinfunction "VDDARM23_IN_7_T9") (pintype "power_in"))
      (node (ref "U1") (pin "U9") (pinfunction "VDDARM23_IN_8_U9") (pintype "power_in"))
    )
    (net (code "5") (name "+2V5") (class "Default")
      (node (ref "C153") (pin "1") (pinfunction "1_1") (pintype "passive"))
      (node (ref "R74") (pin "2") (pinfunction "2_2") (pintype "passive"))
      (node (ref "R78") (pin "2") (pinfunction "2_2") (pintype "passive"))
      (node (ref "R80") (pin "2") (pinfunction "2_2") (pintype "passive"))
    )
    (net (code "6") (name "+3V0_ALWAYS") (class "Default")
      (node (ref "C136") (pin "1") (pinfunction "1_1") (pintype "passive"))
      (node (ref "C137") (pin "1") (pinfunction "1_1") (pintype "passive"))
      (node (ref "C142") (pin "1") (pinfunction "1_1") (pintype "passive"))
      (node (ref "U1") (pin "G11") (pinfunction "VDD_SNVS_IN_G11") (pintype "power_in"))
      (node (ref "U1") (pin "H9") (pinfunction "VDDHIGH_IN_1_H9") (pintype "power_in"))
      (node (ref "U1") (pin "J9") (pinfunction "VDDHIGH_IN_2_J9") (pintype "power_in"))
    )
    (net (code "7") (name "+3V3") (class "Default")
      (node (ref "C144") (pin "1") (pinfunction "1_1") (pintype "passive"))
      (node (ref "C146") (pin "1") (pinfunction "1_1") (pintype "passive"))
      (node (ref "C147") (pin "1") (pinfunction "1_1") (pintype "passive"))
      (node (ref "C148") (pin "1") (pinfunction "1_1") (pintype "passive"))
      (node (ref "C154") (pin "1") (pinfunction "1_1") (pintype "passive"))
      (node (ref "C163") (pin "1") (pinfunction "1_1") (pintype "passive"))
      (node (ref "C164") (pin "1") (pinfunction "1_1") (pintype "passive"))
      (node (ref "C165") (pin "1") (pinfunction "1_1") (pintype "passive"))
      (node (ref "C166") (pin "1") (pinfunction "1_1") (pintype "passive"))
      (node (ref "C174") (pin "1") (pinfunction "1_1") (pintype "passive"))
      (node (ref "R76") (pin "2") (pinfunction "2_2") (pintype "passive"))
      (node (ref "U1") (pin "G14") (pinfunction "NVCC_SD3_G14") (pintype "power_in"))
      (node (ref "U1") (pin "G15") (pinfunction "NVCC_NANDF_G15") (pintype "power_in"))
      (node (ref "U1") (pin "G16") (pinfunction "NVCC_SD1_G16") (pintype "power_in"))
      (node (ref "U1") (pin "G17") (pinfunction "NVCC_SD2_G17") (pintype "power_in"))
      (node (ref "U1") (pin "J7") (pinfunction "NVCC_JTAG_J7") (pintype "power_in"))
      (node (ref "U1") (pin "K19") (pinfunction "NVCC_EIM0_K19") (pintype "power_in"))
      (node (ref "U1") (pin "L19") (pinfunction "NVCC_EIM1_L19") (pintype "power_in"))
      (node (ref "U1") (pin "M19") (pinfunction "NVCC_EIM2_M19") (pintype "power_in"))
      (node (ref "U1") (pin "P19") (pinfunction "NVCC_LCD_P19") (pintype "power_in"))
      (node (ref "U1") (pin "P7") (pinfunction "NVCC_GPIO_P7") (pintype "power_in"))
    )
    (net (code "8") (name "/+1V1_NVCC_PLL_OUT") (class "Default")
      (node (ref "C150") (pin "1") (pinfunction "1_1") (pintype "passive"))
      (node (ref "C151") (pin "1") (pinfunction "1_1") (pintype "passive"))
      (node (ref "R105") (pin "1") (pinfunction "1_1") (pintype "passive"))
      (node (ref "R77") (pin "2") (pinfunction "2_2") (pintype "passive"))
      (node (ref "R79") (pin "2") (pinfunction "2_2") (pintype "passive"))
      (node (ref "U1") (pin "E8") (pinfunction "NVCC_PLL_OUT_E8") (pintype "power_in"))
    )
    (net (code "9") (name "/+1V2_VDD_ARM_CAP") (class "Default")
      (node (ref "C100") (pin "1") (pinfunction "1_1") (pintype "passive"))
      (node (ref "C101") (pin "1") (pinfunction "1_1") (pintype "passive"))
      (node (ref "C102") (pin "1") (pinfunction "1_1") (pintype "passive"))
      (node (ref "C103") (pin "1") (pinfunction "1_1") (pintype "passive"))
      (node (ref "C104") (pin "1") (pinfunction "1_1") (pintype "passive"))
      (node (ref "C105") (pin "1") (pinfunction "1_1") (pintype "passive"))
      (node (ref "C106") (pin "1") (pinfunction "1_1") (pintype "passive"))
      (node (ref "C97") (pin "1") (pinfunction "1_1") (pintype "passive"))
      (node (ref "C98") (pin "1") (pinfunction "1_1") (pintype "passive"))
      (node (ref "C99") (pin "1") (pinfunction "1_1") (pintype "passive"))
      (node (ref "U1") (pin "H11") (pinfunction "VDDARM23_CAP_1_H11") (pintype "power_in"))
      (node (ref "U1") (pin "H13") (pinfunction "VDDARM_CAP_1_H13") (pintype "power_in"))
      (node (ref "U1") (pin "J11") (pinfunction "VDDARM23_CAP_2_J11") (pintype "power_in"))
      (node (ref "U1") (pin "J13") (pinfunction "VDDARM_CAP_2_J13") (pintype "power_in"))
      (node (ref "U1") (pin "K11") (pinfunction "VDDARM23_CAP_3_K11") (pintype "power_in"))
      (node (ref "U1") (pin "K13") (pinfunction "VDDARM_CAP_3_K13") (pintype "power_in"))
      (node (ref "U1") (pin "L11") (pinfunction "VDDARM23_CAP_4_L11") (pintype "power_in"))
      (node (ref "U1") (pin "L13") (pinfunction "VDDARM_CAP_4_L13") (pintype "power_in"))
      (node (ref "U1") (pin "M11") (pinfunction "VDDARM23_CAP_5_M11") (pintype "power_in"))
      (node (ref "U1") (pin "M13") (pinfunction "VDDARM_CAP_5_M13") (pintype "power_in"))
      (node (ref "U1") (pin "N11") (pinfunction "VDDARM23_CAP_6_N11") (pintype "power_in"))
      (node (ref "U1") (pin "N13") (pinfunction "VDDARM_CAP_6_N13") (pintype "power_in"))
      (node (ref "U1") (pin "P11") (pinfunction "VDDARM23_CAP_7_P11") (pintype "power_in"))
      (node (ref "U1") (pin "P13") (pinfunction "VDDARM_CAP_7_P13") (pintype "power_in"))
      (node (ref "U1") (pin "R11") (pinfunction "VDDARM23_CAP_8_R11") (pintype "power_in"))
      (node (ref "U1") (pin "R13") (pinfunction "VDDARM_CAP_8_R13") (pintype "power_in"))
    )
    (net (code "10") (name "/+1V375_VDDSOC_IN") (class "Default")
      (node (ref "C119") (pin "1") (pinfunction "1_1") (pintype "passive"))
      (node (ref "C120") (pin "1") (pinfunction "1_1") (pintype "passive"))
      (node (ref "C121") (pin "1") (pinfunction "1_1") (pintype "passive"))
      (node (ref "C122") (pin "1") (pinfunction "1_1") (pintype "passive"))
      (node (ref "C123") (pin "1") (pinfunction "1_1") (pintype "passive"))
      (node (ref "C124") (pin "1") (pinfunction "1_1") (pintype "passive"))
      (node (ref "C125") (pin "1") (pinfunction "1_1") (pintype "passive"))
      (node (ref "C126") (pin "1") (pinfunction "1_1") (pintype "passive"))
      (node (ref "C127") (pin "1") (pinfunction "1_1") (pintype "passive"))
      (node (ref "C128") (pin "1") (pinfunction "1_1") (pintype "passive"))
      (node (ref "C129") (pin "1") (pinfunction "1_1") (pintype "passive"))
      (node (ref "FB2") (pin "1") (pinfunction "1_1") (pintype "passive"))
      (node (ref "U1") (pin "H16") (pinfunction "VDDSOC_IN_1_H16") (pintype "power_in"))
      (node (ref "U1") (pin "J16") (pinfunction "VDDSOC_IN_2_J16") (pintype "power_in"))
      (node (ref "U1") (pin "K16") (pinfunction "VDDSOC_IN_3_K16") (pintype "power_in"))
      (node (ref "U1") (pin "L16") (pinfunction "VDDSOC_IN_4_L16") (pintype "power_in"))
      (node (ref "U1") (pin "M16") (pinfunction "VDDSOC_IN_5_M16") (pintype "power_in"))
      (node (ref "U1") (pin "N16") (pinfunction "VDDSOC_IN_6_N16") (pintype "power_in"))
      (node (ref "U1") (pin "P16") (pinfunction "VDDSOC_IN_7_P16") (pintype "power_in"))
      (node (ref "U1") (pin "R16") (pinfunction "VDDSOC_IN_8_R16") (pintype "power_in"))
      (node (ref "U1") (pin "T16") (pinfunction "VDDSOC_IN_9_T16") (pintype "power_in"))
      (node (ref "U1") (pin "U16") (pinfunction "VDDSOC_IN_10_U16") (pintype "power_in"))
    )
    (net (code "11") (name "/+2V5_VDDHIGH_VPH") (class "Default")
      (node (ref "C139") (pin "2") (pinfunction "2_2") (pintype "passive"))
      (node (ref "C140") (pin "1") (pinfunction "1_1") (pintype "passive"))
      (node (ref "C141") (pin "1") (pinfunction "1_1") (pintype "passive"))
      (node (ref "U1") (pin "H10") (pinfunction "VDDHIGH_CAP_1_H10") (pintype "power_in"))
      (node (ref "U1") (pin "J10") (pinfunction "VDDHIGH_CAP_2_J10") (pintype "power_in"))
    )
    (net (code "12") (name "/+NVCC_CSI") (class "Default")
      (node (ref "C145") (pin "1") (pinfunction "1_1") (pintype "passive"))
      (node (ref "R76") (pin "1") (pinfunction "1_1") (pintype "passive"))
      (node (ref "U1") (pin "N7") (pinfunction "NVCC_CSI_N7") (pintype "power_in"))
    )
    (net (code "13") (name "/+NVCC_ENET") (class "Default")
      (node (ref "C155") (pin "1") (pinfunction "1_1") (pintype "passive"))
      (node (ref "C156") (pin "1") (pinfunction "1_1") (pintype "passive"))
      (node (ref "R74") (pin "1") (pinfunction "1_1") (pintype "passive"))
      (node (ref "U1") (pin "R19") (pinfunction "NVCC_ENET_R19") (pintype "power_in"))
    )
    (net (code "14") (name "/+NVCC_MIPI") (class "Default")
      (node (ref "C149") (pin "1") (pinfunction "1_1") (pintype "passive"))
      (node (ref "R78") (pin "1") (pinfunction "1_1") (pintype "passive"))
      (node (ref "U1") (pin "K7") (pinfunction "NVCC_MIPI_K7") (pintype "power_in"))
    )
    (net (code "15") (name "/+NVCC_RGMII") (class "Default")
      (node (ref "C152") (pin "1") (pinfunction "1_1") (pintype "passive"))
      (node (ref "R80") (pin "1") (pinfunction "1_1") (pintype "passive"))
      (node (ref "U1") (pin "G18") (pinfunction "NVCC_RGMII_G18") (pintype "power_in"))
    )
    (net (code "16") (name "/+VDDPU") (class "Default")
      (node (ref "C130") (pin "1") (pinfunction "1_1") (pintype "passive"))
      (node (ref "C131") (pin "1") (pinfunction "1_1") (pintype "passive"))
      (node (ref "C132") (pin "1") (pinfunction "1_1") (pintype "passive"))
      (node (ref "C133") (pin "1") (pinfunction "1_1") (pintype "passive"))
      (node (ref "C134") (pin "1") (pinfunction "1_1") (pintype "passive"))
      (node (ref "C135") (pin "1") (pinfunction "1_1") (pintype "passive"))
      (node (ref "U1") (pin "H17") (pinfunction "VDDPU_CAP_1_H17") (pintype "power_in"))
      (node (ref "U1") (pin "J17") (pinfunction "VDDPU_CAP_2_J17") (pintype "power_in"))
      (node (ref "U1") (pin "K17") (pinfunction "VDDPU_CAP_3_K17") (pintype "power_in"))
      (node (ref "U1") (pin "L17") (pinfunction "VDDPU_CAP_4_L17") (pintype "power_in"))
      (node (ref "U1") (pin "M17") (pinfunction "VDDPU_CAP_5_M17") (pintype "power_in"))
      (node (ref "U1") (pin "N17") (pinfunction "VDDPU_CAP_6_N17") (pintype "power_in"))
      (node (ref "U1") (pin "P17") (pinfunction "VDDPU_CAP_7_P17") (pintype "power_in"))
    )
    (net (code "17") (name "/+VDD_SNVS_CAP") (class "Default")
      (node (ref "C143") (pin "1") (pinfunction "1_1") (pintype "passive"))
      (node (ref "U1") (pin "G9") (pinfunction "VDD_SNVS_CAP_G9") (pintype "power_in"))
    )
    (net (code "18") (name "GND") (class "Default")
      (node (ref "C100") (pin "2") (pinfunction "2_2") (pintype "passive"))
      (node (ref "C101") (pin "2") (pinfunction "2_2") (pintype "passive"))
      (node (ref "C102") (pin "2") (pinfunction "2_2") (pintype "passive"))
      (node (ref "C103") (pin "2") (pinfunction "2_2") (pintype "passive"))
      (node (ref "C104") (pin "2") (pinfunction "2_2") (pintype "passive"))
      (node (ref "C105") (pin "2") (pinfunction "2_2") (pintype "passive"))
      (node (ref "C106") (pin "2") (pinfunction "2_2") (pintype "passive"))
      (node (ref "C107") (pin "2") (pinfunction "2_2") (pintype "passive"))
      (node (ref "C108") (pin "2") (pinfunction "2_2") (pintype "passive"))
      (node (ref "C109") (pin "2") (pinfunction "2_2") (pintype "passive"))
      (node (ref "C110") (pin "2") (pinfunction "2_2") (pintype "passive"))
      (node (ref "C111") (pin "2") (pinfunction "2_2") (pintype "passive"))
      (node (ref "C112") (pin "2") (pinfunction "2_2") (pintype "passive"))
      (node (ref "C113") (pin "2") (pinfunction "2_2") (pintype "passive"))
      (node (ref "C114") (pin "2") (pinfunction "2_2") (pintype "passive"))
      (node (ref "C115") (pin "2") (pinfunction "2_2") (pintype "passive"))
      (node (ref "C116") (pin "2") (pinfunction "2_2") (pintype "passive"))
      (node (ref "C117") (pin "2") (pinfunction "2_2") (pintype "passive"))
      (node (ref "C118") (pin "2") (pinfunction "2_2") (pintype "passive"))
      (node (ref "C119") (pin "2") (pinfunction "2_2") (pintype "passive"))
      (node (ref "C120") (pin "2") (pinfunction "2_2") (pintype "passive"))
      (node (ref "C121") (pin "2") (pinfunction "2_2") (pintype "passive"))
      (node (ref "C122") (pin "2") (pinfunction "2_2") (pintype "passive"))
      (node (ref "C123") (pin "2") (pinfunction "2_2") (pintype "passive"))
      (node (ref "C124") (pin "2") (pinfunction "2_2") (pintype "passive"))
      (node (ref "C125") (pin "2") (pinfunction "2_2") (pintype "passive"))
      (node (ref "C126") (pin "2") (pinfunction "2_2") (pintype "passive"))
      (node (ref "C127") (pin "2") (pinfunction "2_2") (pintype "passive"))
      (node (ref "C128") (pin "2") (pinfunction "2_2") (pintype "passive"))
      (node (ref "C129") (pin "2") (pinfunction "2_2") (pintype "passive"))
      (node (ref "C130") (pin "2") (pinfunction "2_2") (pintype "passive"))
      (node (ref "C131") (pin "2") (pinfunction "2_2") (pintype "passive"))
      (node (ref "C132") (pin "2") (pinfunction "2_2") (pintype "passive"))
      (node (ref "C133") (pin "2") (pinfunction "2_2") (pintype "passive"))
      (node (ref "C134") (pin "2") (pinfunction "2_2") (pintype "passive"))
      (node (ref "C135") (pin "2") (pinfunction "2_2") (pintype "passive"))
      (node (ref "C136") (pin "2") (pinfunction "2_2") (pintype "passive"))
      (node (ref "C137") (pin "2") (pinfunction "2_2") (pintype "passive"))
      (node (ref "C138") (pin "2") (pinfunction "2_2") (pintype "passive"))
      (node (ref "C139") (pin "1") (pinfunction "1_1") (pintype "passive"))
      (node (ref "C140") (pin "2") (pinfunction "2_2") (pintype "passive"))
      (node (ref "C141") (pin "2") (pinfunction "2_2") (pintype "passive"))
      (node (ref "C142") (pin "2") (pinfunction "2_2") (pintype "passive"))
      (node (ref "C143") (pin "2") (pinfunction "2_2") (pintype "passive"))
      (node (ref "C144") (pin "2") (pinfunction "2_2") (pintype "passive"))
      (node (ref "C145") (pin "2") (pinfunction "2_2") (pintype "passive"))
      (node (ref "C146") (pin "2") (pinfunction "2_2") (pintype "passive"))
      (node (ref "C147") (pin "2") (pinfunction "2_2") (pintype "passive"))
      (node (ref "C148") (pin "2") (pinfunction "2_2") (pintype "passive"))
      (node (ref "C149") (pin "2") (pinfunction "2_2") (pintype "passive"))
      (node (ref "C150") (pin "2") (pinfunction "2_2") (pintype "passive"))
      (node (ref "C151") (pin "2") (pinfunction "2_2") (pintype "passive"))
      (node (ref "C152") (pin "2") (pinfunction "2_2") (pintype "passive"))
      (node (ref "C153") (pin "2") (pinfunction "2_2") (pintype "passive"))
      (node (ref "C154") (pin "2") (pinfunction "2_2") (pintype "passive"))
      (node (ref "C155") (pin "2") (pinfunction "2_2") (pintype "passive"))
      (node (ref "C156") (pin "2") (pinfunction "2_2") (pintype "passive"))
      (node (ref "C157") (pin "2") (pinfunction "2_2") (pintype "passive"))
      (node (ref "C158") (pin "2") (pinfunction "2_2") (pintype "passive"))
      (node (ref "C159") (pin "2") (pinfunction "2_2") (pintype "passive"))
      (node (ref "C160") (pin "2") (pinfunction "2_2") (pintype "passive"))
      (node (ref "C161") (pin "2") (pinfunction "2_2") (pintype "passive"))
      (node (ref "C162") (pin "2") (pinfunction "2_2") (pintype "passive"))
      (node (ref "C163") (pin "2") (pinfunction "2_2") (pintype "passive"))
      (node (ref "C164") (pin "2") (pinfunction "2_2") (pintype "passive"))
      (node (ref "C165") (pin "2") (pinfunction "2_2") (pintype "passive"))
      (node (ref "C166") (pin "2") (pinfunction "2_2") (pintype "passive"))
      (node (ref "C167") (pin "2") (pinfunction "2_2") (pintype "passive"))
      (node (ref "C168") (pin "2") (pinfunction "2_2") (pintype "passive"))
      (node (ref "C169") (pin "2") (pinfunction "2_2") (pintype "passive"))
      (node (ref "C170") (pin "2") (pinfunction "2_2") (pintype "passive"))
      (node (ref "C171") (pin "2") (pinfunction "2_2") (pintype "passive"))
      (node (ref "C172") (pin "2") (pinfunction "2_2") (pintype "passive"))
      (node (ref "C173") (pin "2") (pinfunction "2_2") (pintype "passive"))
      (node (ref "C174") (pin "2") (pinfunction "2_2") (pintype "passive"))
      (node (ref "C90") (pin "2") (pinfunction "2_2") (pintype "passive"))
      (node (ref "C91") (pin "2") (pinfunction "2_2") (pintype "passive"))
      (node (ref "C92") (pin "2") (pinfunction "2_2") (pintype "passive"))
      (node (ref "C93") (pin "2") (pinfunction "2_2") (pintype "passive"))
      (node (ref "C94") (pin "2") (pinfunction "2_2") (pintype "passive"))
      (node (ref "C95") (pin "2") (pinfunction "2_2") (pintype "passive"))
      (node (ref "C96") (pin "2") (pinfunction "2_2") (pintype "passive"))
      (node (ref "C97") (pin "2") (pinfunction "2_2") (pintype "passive"))
      (node (ref "C98") (pin "2") (pinfunction "2_2") (pintype "passive"))
      (node (ref "C99") (pin "2") (pinfunction "2_2") (pintype "passive"))
      (node (ref "R79") (pin "1") (pinfunction "1_1") (pintype "passive"))
      (node (ref "U1") (pin "A13") (pinfunction "GND_1_A13") (pintype "power_in"))
      (node (ref "U1") (pin "A25") (pinfunction "GND_2_A25") (pintype "power_in"))
      (node (ref "U1") (pin "A4") (pinfunction "GND_3_A4") (pintype "power_in"))
      (node (ref "U1") (pin "A5") (pinfunction "FA_ANA_A5") (pintype "power_in"))
      (node (ref "U1") (pin "A8") (pinfunction "GND_4_A8") (pintype "power_in"))
      (node (ref "U1") (pin "AA10") (pinfunction "GND_5_AA10") (pintype "power_in"))
      (node (ref "U1") (pin "AA13") (pinfunction "GND_6_AA13") (pintype "power_in"))
      (node (ref "U1") (pin "AA16") (pinfunction "GND_7_AA16") (pintype "power_in"))
      (node (ref "U1") (pin "AA19") (pinfunction "GND_8_AA19") (pintype "power_in"))
      (node (ref "U1") (pin "AA22") (pinfunction "GND_9_AA22") (pintype "power_in"))
      (node (ref "U1") (pin "AA7") (pinfunction "GND_10_AA7") (pintype "power_in"))
      (node (ref "U1") (pin "AB24") (pinfunction "GND_11_AB24") (pintype "power_in"))
      (node (ref "U1") (pin "AB3") (pinfunction "GND_12_AB3") (pintype "power_in"))
      (node (ref "U1") (pin "AD10") (pinfunction "GND_13_AD10") (pintype "power_in"))
      (node (ref "U1") (pin "AD13") (pinfunction "GND_14_AD13") (pintype "power_in"))
      (node (ref "U1") (pin "AD16") (pinfunction "GND_15_AD16") (pintype "power_in"))
      (node (ref "U1") (pin "AD19") (pinfunction "GND_16_AD19") (pintype "power_in"))
      (node (ref "U1") (pin "AD22") (pinfunction "GND_17_AD22") (pintype "power_in"))
      (node (ref "U1") (pin "AD4") (pinfunction "GND_18_AD4") (pintype "power_in"))
      (node (ref "U1") (pin "AD7") (pinfunction "GND_19_AD7") (pintype "power_in"))
      (node (ref "U1") (pin "AE1") (pinfunction "GND_20_AE1") (pintype "power_in"))
      (node (ref "U1") (pin "AE25") (pinfunction "GND_21_AE25") (pintype "power_in"))
      (node (ref "U1") (pin "B4") (pinfunction "GND_22_B4") (pintype "power_in"))
      (node (ref "U1") (pin "B5") (pinfunction "VDD_FA_B5") (pintype "power_in"))
      (node (ref "U1") (pin "C1") (pinfunction "GND_23_C1") (pintype "power_in"))
      (node (ref "U1") (pin "C10") (pinfunction "GND_24_C10") (pintype "power_in"))
      (node (ref "U1") (pin "C4") (pinfunction "GND_25_C4") (pintype "power_in"))
      (node (ref "U1") (pin "C6") (pinfunction "GND_26_C6") (pintype "power_in"))
      (node (ref "U1") (pin "D3") (pinfunction "GND_27_D3") (pintype "power_in"))
      (node (ref "U1") (pin "D6") (pinfunction "GND_28_D6") (pintype "power_in"))
      (node (ref "U1") (pin "D8") (pinfunction "GND_29_D8") (pintype "power_in"))
      (node (ref "U1") (pin "E5") (pinfunction "GND_30_E5") (pintype "power_in"))
      (node (ref "U1") (pin "E6") (pinfunction "GND_31_E6") (pintype "power_in"))
      (node (ref "U1") (pin "E7") (pinfunction "GND_32_E7") (pintype "power_in"))
      (node (ref "U1") (pin "F5") (pinfunction "GND_33_F5") (pintype "power_in"))
      (node (ref "U1") (pin "F6") (pinfunction "GND_34_F6") (pintype "power_in"))
      (node (ref "U1") (pin "F7") (pinfunction "GND_35_F7") (pintype "power_in"))
      (node (ref "U1") (pin "F8") (pinfunction "GND_36_F8") (pintype "power_in"))
      (node (ref "U1") (pin "G10") (pinfunction "GND_37_G10") (pintype "power_in"))
      (node (ref "U1") (pin "G19") (pinfunction "GND_38_G19") (pintype "power_in"))
      (node (ref "U1") (pin "G3") (pinfunction "GND_39_G3") (pintype "power_in"))
      (node (ref "U1") (pin "H12") (pinfunction "GND_40_H12") (pintype "power_in"))
      (node (ref "U1") (pin "H15") (pinfunction "GND_41_H15") (pintype "power_in"))
      (node (ref "U1") (pin "H18") (pinfunction "GND_42_H18") (pintype "power_in"))
      (node (ref "U1") (pin "H8") (pinfunction "GND_43_H8") (pintype "power_in"))
      (node (ref "U1") (pin "J12") (pinfunction "GND_44_J12") (pintype "power_in"))
      (node (ref "U1") (pin "J15") (pinfunction "GND_45_J15") (pintype "power_in"))
      (node (ref "U1") (pin "J18") (pinfunction "GND_46_J18") (pintype "power_in"))
      (node (ref "U1") (pin "J2") (pinfunction "GND_47_J2") (pintype "power_in"))
      (node (ref "U1") (pin "J8") (pinfunction "GND_48_J8") (pintype "power_in"))
      (node (ref "U1") (pin "K10") (pinfunction "GND_49_K10") (pintype "power_in"))
      (node (ref "U1") (pin "K12") (pinfunction "GND_50_K12") (pintype "power_in"))
      (node (ref "U1") (pin "K15") (pinfunction "GND_51_K15") (pintype "power_in"))
      (node (ref "U1") (pin "K18") (pinfunction "GND_52_K18") (pintype "power_in"))
      (node (ref "U1") (pin "K8") (pinfunction "GND_53_K8") (pintype "power_in"))
      (node (ref "U1") (pin "L10") (pinfunction "GND_54_L10") (pintype "power_in"))
      (node (ref "U1") (pin "L12") (pinfunction "GND_55_L12") (pintype "power_in"))
      (node (ref "U1") (pin "L15") (pinfunction "GND_56_L15") (pintype "power_in"))
      (node (ref "U1") (pin "L18") (pinfunction "GND_57_L18") (pintype "power_in"))
      (node (ref "U1") (pin "L2") (pinfunction "GND_58_L2") (pintype "power_in"))
      (node (ref "U1") (pin "L5") (pinfunction "GND_59_L5") (pintype "power_in"))
      (node (ref "U1") (pin "L8") (pinfunction "GND_60_L8") (pintype "power_in"))
      (node (ref "U1") (pin "M10") (pinfunction "GND_61_M10") (pintype "power_in"))
      (node (ref "U1") (pin "M12") (pinfunction "GND_62_M12") (pintype "power_in"))
      (node (ref "U1") (pin "M15") (pinfunction "GND_63_M15") (pintype "power_in"))
      (node (ref "U1") (pin "M18") (pinfunction "GND_64_M18") (pintype "power_in"))
      (node (ref "U1") (pin "M8") (pinfunction "GND_65_M8") (pintype "power_in"))
      (node (ref "U1") (pin "N10") (pinfunction "GND_66_N10") (pintype "power_in"))
      (node (ref "U1") (pin "N15") (pinfunction "GND_67_N15") (pintype "power_in"))
      (node (ref "U1") (pin "N18") (pinfunction "GND_68_N18") (pintype "power_in"))
      (node (ref "U1") (pin "N8") (pinfunction "GND_69_N8") (pintype "power_in"))
      (node (ref "U1") (pin "P10") (pinfunction "GND_70_P10") (pintype "power_in"))
      (node (ref "U1") (pin "P12") (pinfunction "GND_71_P12") (pintype "power_in"))
      (node (ref "U1") (pin "P15") (pinfunction "GND_72_P15") (pintype "power_in"))
      (node (ref "U1") (pin "P18") (pinfunction "GND_73_P18") (pintype "power_in"))
      (node (ref "U1") (pin "P8") (pinfunction "GND_74_P8") (pintype "power_in"))
      (node (ref "U1") (pin "R12") (pinfunction "GND_75_R12") (pintype "power_in"))
      (node (ref "U1") (pin "R15") (pinfunction "GND_76_R15") (pintype "power_in"))
      (node (ref "U1") (pin "R17") (pinfunction "GND_77_R17") (pintype "power_in"))
      (node (ref "U1") (pin "R8") (pinfunction "GND_78_R8") (pintype "power_in"))
      (node (ref "U1") (pin "T11") (pinfunction "GND_79_T11") (pintype "power_in"))
      (node (ref "U1") (pin "T12") (pinfunction "GND_80_T12") (pintype "power_in"))
      (node (ref "U1") (pin "T15") (pinfunction "GND_81_T15") (pintype "power_in"))
      (node (ref "U1") (pin "T17") (pinfunction "GND_82_T17") (pintype "power_in"))
      (node (ref "U1") (pin "T19") (pinfunction "GND_83_T19") (pintype "power_in"))
      (node (ref "U1") (pin "T8") (pinfunction "GND_84_T8") (pintype "power_in"))
      (node (ref "U1") (pin "U11") (pinfunction "GND_85_U11") (pintype "power_in"))
      (node (ref "U1") (pin "U12") (pinfunction "GND_86_U12") (pintype "power_in"))
      (node (ref "U1") (pin "U15") (pinfunction "GND_87_U15") (pintype "power_in"))
      (node (ref "U1") (pin "U17") (pinfunction "GND_88_U17") (pintype "power_in"))
      (node (ref "U1") (pin "U19") (pinfunction "GND_90_U19") (pintype "power_in"))
      (node (ref "U1") (pin "U8") (pinfunction "GND_89_U8") (pintype "power_in"))
      (node (ref "U1") (pin "V19") (pinfunction "GND_92_V19") (pintype "power_in"))
      (node (ref "U1") (pin "V8") (pinfunction "GND_91_V8") (pintype "power_in"))
      (node (ref "U1") (pin "W10") (pinfunction "GND_97_W10") (pintype "power_in"))
      (node (ref "U1") (pin "W11") (pinfunction "GND_98_W11") (pintype "power_in"))
      (node (ref "U1") (pin "W12") (pinfunction "GND_99_W12") (pintype "power_in"))
      (node (ref "U1") (pin "W13") (pinfunction "GND_100_W13") (pintype "power_in"))
      (node (ref "U1") (pin "W15") (pinfunction "GND_101_W15") (pintype "power_in"))
      (node (ref "U1") (pin "W16") (pinfunction "GND_102_W16") (pintype "power_in"))
      (node (ref "U1") (pin "W17") (pinfunction "GND_103_W17") (pintype "power_in"))
      (node (ref "U1") (pin "W18") (pinfunction "GND_104_W18") (pintype "power_in"))
      (node (ref "U1") (pin "W19") (pinfunction "GND_105_W19") (pintype "power_in"))
      (node (ref "U1") (pin "W3") (pinfunction "GND_93_W3") (pintype "power_in"))
      (node (ref "U1") (pin "W7") (pinfunction "GND_94_W7") (pintype "power_in"))
      (node (ref "U1") (pin "W8") (pinfunction "GND_95_W8") (pintype "power_in"))
      (node (ref "U1") (pin "W9") (pinfunction "GND_96_W9") (pintype "power_in"))
      (node (ref "U1") (pin "Y24") (pinfunction "GND_107_Y24") (pintype "power_in"))
      (node (ref "U1") (pin "Y5") (pinfunction "GND_106_Y5") (pintype "power_in"))
    )
    (net (code "19") (name "unconnected-(U1B-GPANAIO-PadC8)") (class "Default")
      (node (ref "U1") (pin "C8") (pinfunction "GPANAIO_C8") (pintype "power_in+no_connect"))
    )
  )
)
